# cougar_mmjoy.net
KiCad netlist of a schematic drawn in EAGLE
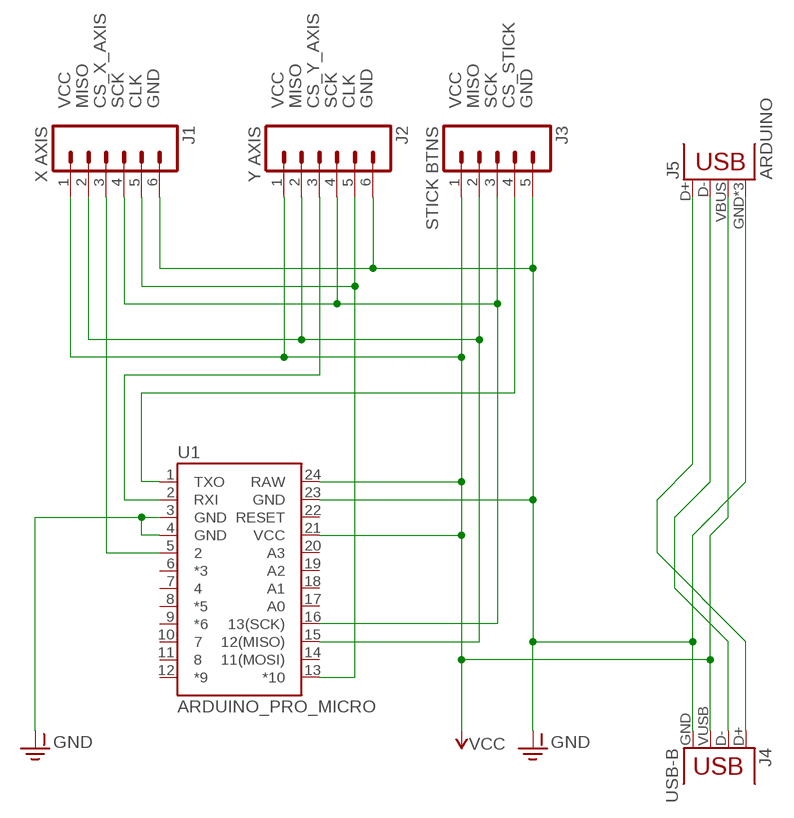
[diagram p0: schematic, sheet 1]

(export (version "E")
  (design (tool "Eeschema 10.0.6"))
  (components
    (comp (ref "J1")
      (value "X AXIS")
      (footprint "eagle-import:MOLEX-1X6_LOCK")
      (libsource (lib "eagle-import") (part "M06POLAR_LOCK"))
    )
    (comp (ref "J2")
      (value "Y AXIS")
      (footprint "eagle-import:MOLEX-1X6_LOCK")
      (libsource (lib "eagle-import") (part "M06POLAR_LOCK"))
    )
    (comp (ref "J3")
      (value "STICK BTNS")
      (footprint "eagle-import:1X05_LOCK")
      (libsource (lib "eagle-import") (part "M05LOCK"))
    )
    (comp (ref "J4")
      (value "USB-B")
      (footprint "eagle-import:USB-B-SMT")
      (libsource (lib "eagle-import") (part "USB-B-S"))
    )
    (comp (ref "J5")
      (value "ARDUINO")
      (footprint "eagle-import:USB-MICROB")
      (libsource (lib "eagle-import") (part "USB-MICROB"))
    )
    (comp (ref "U1")
      (value "ARDUINO_PRO_MICRO")
      (footprint "eagle-import:ARDUINO_PRO_MICRO")
      (libsource (lib "eagle-import") (part "ARDUINO_PRO_MICRO"))
    )
  )
  (nets
    (net (code "1") (name "/CLK") (class "Default")
      (node (ref "J1") (pin "5") (pinfunction "5_5") (pintype "passive"))
      (node (ref "J2") (pin "5") (pinfunction "5_5") (pintype "passive"))
      (node (ref "U1") (pin "13") (pinfunction "*10_13") (pintype "bidirectional"))
    )
    (net (code "2") (name "/CS_STICK") (class "Default")
      (node (ref "J3") (pin "4") (pinfunction "4_4") (pintype "passive"))
      (node (ref "U1") (pin "1") (pinfunction "TXO_1") (pintype "bidirectional"))
    )
    (net (code "3") (name "/CS_X_AXIS") (class "Default")
      (node (ref "J1") (pin "3") (pinfunction "3_3") (pintype "passive"))
      (node (ref "U1") (pin "5") (pinfunction "2_5") (pintype "bidirectional"))
    )
    (net (code "4") (name "/CS_Y_AXIS") (class "Default")
      (node (ref "J2") (pin "3") (pinfunction "3_3") (pintype "passive"))
      (node (ref "U1") (pin "2") (pinfunction "RXI_2") (pintype "bidirectional"))
    )
    (net (code "5") (name "/MISO") (class "Default")
      (node (ref "J1") (pin "2") (pinfunction "2_2") (pintype "passive"))
      (node (ref "J2") (pin "2") (pinfunction "2_2") (pintype "passive"))
      (node (ref "J3") (pin "2") (pinfunction "2_2") (pintype "passive"))
      (node (ref "U1") (pin "15") (pinfunction "12(MISO)_15") (pintype "bidirectional"))
    )
    (net (code "6") (name "/SCK") (class "Default")
      (node (ref "J1") (pin "4") (pinfunction "4_4") (pintype "passive"))
      (node (ref "J2") (pin "4") (pinfunction "4_4") (pintype "passive"))
      (node (ref "J3") (pin "3") (pinfunction "3_3") (pintype "passive"))
      (node (ref "U1") (pin "16") (pinfunction "13(SCK)_16") (pintype "bidirectional"))
    )
    (net (code "7") (name "GND") (class "Default")
      (node (ref "J1") (pin "6") (pinfunction "6_6") (pintype "passive"))
      (node (ref "J2") (pin "6") (pinfunction "6_6") (pintype "passive"))
      (node (ref "J3") (pin "5") (pinfunction "5_5") (pintype "passive"))
      (node (ref "J4") (pin "GND") (pinfunction "GND_GND") (pintype "bidirectional"))
      (node (ref "J5") (pin "GND") (pinfunction "GND_GND") (pintype "bidirectional"))
      (node (ref "J5") (pin "MT1") (pinfunction "GND_MT1") (pintype "bidirectional"))
      (node (ref "J5") (pin "MT2") (pinfunction "GND_MT2") (pintype "bidirectional"))
      (node (ref "U1") (pin "23") (pinfunction "GND_23") (pintype "bidirectional"))
      (node (ref "U1") (pin "3") (pinfunction "GND_3") (pintype "bidirectional"))
      (node (ref "U1") (pin "4") (pinfunction "GND_4") (pintype "bidirectional"))
    )
    (net (code "8") (name "Net-(J4-PadD+)") (class "Default")
      (node (ref "J4") (pin "D+") (pinfunction "D+_D+") (pintype "bidirectional"))
      (node (ref "J5") (pin "D+") (pinfunction "D+_D+") (pintype "bidirectional"))
    )
    (net (code "9") (name "Net-(J4-PadD-)") (class "Default")
      (node (ref "J4") (pin "D-") (pinfunction "D-_D-") (pintype "bidirectional"))
      (node (ref "J5") (pin "D-") (pinfunction "D-_D-") (pintype "bidirectional"))
    )
    (net (code "10") (name "VCC") (class "Default")
      (node (ref "J1") (pin "1") (pinfunction "1_1") (pintype "passive"))
      (node (ref "J2") (pin "1") (pinfunction "1_1") (pintype "passive"))
      (node (ref "J3") (pin "1") (pinfunction "1_1") (pintype "passive"))
      (node (ref "J4") (pin "VUSB") (pinfunction "VBUS_VUSB") (pintype "bidirectional"))
      (node (ref "J5") (pin "VBUS") (pinfunction "VBUS_VBUS") (pintype "bidirectional"))
      (node (ref "U1") (pin "21") (pinfunction "VCC_21") (pintype "bidirectional"))
      (node (ref "U1") (pin "24") (pinfunction "RAW_24") (pintype "bidirectional"))
    )
    (net (code "11") (name "unconnected-(U1-*3-Pad6)") (class "Default")
      (node (ref "U1") (pin "6") (pinfunction "*3_6") (pintype "bidirectional"))
    )
    (net (code "12") (name "unconnected-(U1-*5-Pad8)") (class "Default")
      (node (ref "U1") (pin "8") (pinfunction "*5_8") (pintype "bidirectional"))
    )
    (net (code "13") (name "unconnected-(U1-*6-Pad9)") (class "Default")
      (node (ref "U1") (pin "9") (pinfunction "*6_9") (pintype "bidirectional"))
    )
    (net (code "14") (name "unconnected-(U1-*9-Pad12)") (class "Default")
      (node (ref "U1") (pin "12") (pinfunction "*9_12") (pintype "bidirectional"))
    )
    (net (code "15") (name "unconnected-(U1-4-Pad7)") (class "Default")
      (node (ref "U1") (pin "7") (pinfunction "4_7") (pintype "bidirectional"))
    )
    (net (code "16") (name "unconnected-(U1-7-Pad10)") (class "Default")
      (node (ref "U1") (pin "10") (pinfunction "7_10") (pintype "bidirectional"))
    )
    (net (code "17") (name "unconnected-(U1-8-Pad11)") (class "Default")
      (node (ref "U1") (pin "11") (pinfunction "8_11") (pintype "bidirectional"))
    )
    (net (code "18") (name "unconnected-(U1-11(MOSI)-Pad14)") (class "Default")
      (node (ref "U1") (pin "14") (pinfunction "11(MOSI)_14") (pintype "bidirectional"))
    )
    (net (code "19") (name "unconnected-(U1-A0-Pad17)") (class "Default")
      (node (ref "U1") (pin "17") (pinfunction "A0_17") (pintype "bidirectional"))
    )
    (net (code "20") (name "unconnected-(U1-A1-Pad18)") (class "Default")
      (node (ref "U1") (pin "18") (pinfunction "A1_18") (pintype "bidirectional"))
    )
    (net (code "21") (name "unconnected-(U1-A2-Pad19)") (class "Default")
      (node (ref "U1") (pin "19") (pinfunction "A2_19") (pintype "bidirectional"))
    )
    (net (code "22") (name "unconnected-(U1-A3-Pad20)") (class "Default")
      (node (ref "U1") (pin "20") (pinfunction "A3_20") (pintype "bidirectional"))
    )
    (net (code "23") (name "unconnected-(U1-RESET-Pad22)") (class "Default")
      (node (ref "U1") (pin "22") (pinfunction "RESET_22") (pintype "bidirectional"))
    )
  )
)
